# 3VSupply.net
KiCad netlist of a schematic drawn in Altium Designer
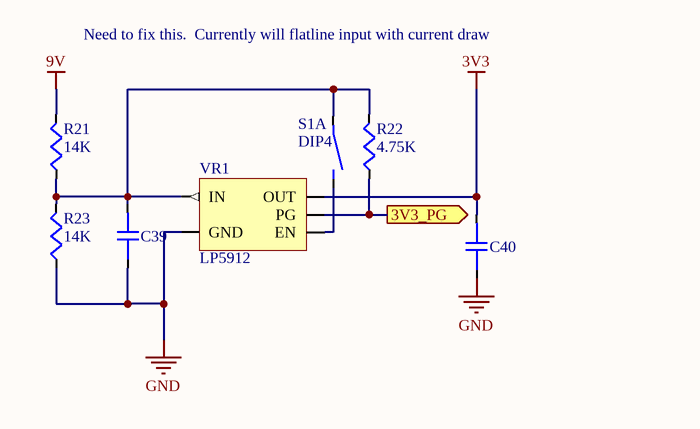
[diagram p0: 3VSupply.SchDoc]

(export (version "E")
  (design (tool "Eeschema 10.0.6"))
  (components
    (comp (ref "C39")
      (value "1uF")
      (description "Cap Ceramic 1uF 16V X7R 10% SMD 0603 125C T/R")
      (fields (field (name "TOLERANCE") "10%") (field (name "VOLTAGE") "16V"))
      (libsource (lib "DAQ") (part "CL10B105KO8NNNC"))
    )
    (comp (ref "C40")
      (value "1uF")
      (description "Cap Ceramic 1uF 16V X7R 10% SMD 0603 125C T/R")
      (fields (field (name "TOLERANCE") "10%") (field (name "VOLTAGE") "16V"))
      (libsource (lib "DAQ") (part "CL10B105KO8NNNC"))
    )
    (comp (ref "R21")
      (value "14K")
      (description "Res Thin Film 0603 14K Ohm 0.1% 1/10W ±25ppm/°C Molded SMD SMD Paper T/R")
      (fields (field (name "TOLERANCE") "0.1%"))
      (libsource (lib "DAQ") (part "TNPW060314K0BEEA"))
    )
    (comp (ref "R22")
      (value "4.75K")
      (description "Res Thin Film 0603 4.75K Ohm 0.1% 1/10W ±25ppm/°C Molded SMD SMD Paper T/R")
      (fields (field (name "TOLERANCE") "0.1%"))
      (libsource (lib "DAQ") (part "TNPW06034K75BEEA"))
    )
    (comp (ref "R23")
      (value "14K")
      (description "Res Thin Film 0603 14K Ohm 0.1% 1/10W ±25ppm/°C Molded SMD SMD Paper T/R")
      (fields (field (name "TOLERANCE") "0.1%"))
      (libsource (lib "DAQ") (part "TNPW060314K0BEEA"))
    )
    (comp (ref "S1")
      (value "DIP4")
      (description "SWITCH DIP TAPE SEALED 4POS 24V")
      (libsource (lib "DAQ") (part "SDA04H0SBR"))
    )
    (comp (ref "VR1")
      (value "LP5912")
      (description "IC REG LINEAR 3.3V 500MA 6SON")
      (libsource (lib "DAQ") (part "LP5912-3.3DRVT"))
    )
  )
  (nets
    (net (code "1") (name "/3V3_PG") (class "Default")
      (node (ref "R22") (pin "1") (pinfunction "1_1") (pintype "passive"))
      (node (ref "VR1") (pin "3") (pinfunction "PG_3") (pintype "passive"))
    )
    (net (code "2") (name "3V3") (class "Default")
      (node (ref "C40") (pin "1") (pinfunction "1_1") (pintype "passive"))
      (node (ref "VR1") (pin "1") (pinfunction "OUT_1") (pintype "passive"))
    )
    (net (code "3") (name "9V") (class "Default")
      (node (ref "R21") (pin "2") (pinfunction "2_2") (pintype "passive"))
    )
    (net (code "4") (name "GND") (class "Default")
      (node (ref "C39") (pin "2") (pinfunction "2_2") (pintype "passive"))
      (node (ref "C40") (pin "2") (pinfunction "2_2") (pintype "passive"))
      (node (ref "R23") (pin "1") (pinfunction "1_1") (pintype "passive"))
      (node (ref "VR1") (pin "5") (pinfunction "GND_5") (pintype "passive"))
    )
    (net (code "5") (name "Net-(VR1-EN)") (class "Default")
      (node (ref "S1") (pin "2") (pinfunction "2_2") (pintype "passive"))
      (node (ref "VR1") (pin "4") (pinfunction "EN_4") (pintype "passive"))
    )
    (net (code "6") (name "Net-(VR1-IN)") (class "Default")
      (node (ref "C39") (pin "1") (pinfunction "1_1") (pintype "passive"))
      (node (ref "R21") (pin "1") (pinfunction "1_1") (pintype "passive"))
      (node (ref "R22") (pin "2") (pinfunction "2_2") (pintype "passive"))
      (node (ref "R23") (pin "2") (pinfunction "2_2") (pintype "passive"))
      (node (ref "S1") (pin "1") (pinfunction "1_1") (pintype "passive"))
      (node (ref "VR1") (pin "6") (pinfunction "IN_6") (pintype "output"))
    )
  )
)
